# AUDIO_LINEOUT.net
KiCad netlist of a schematic drawn in Altium Designer
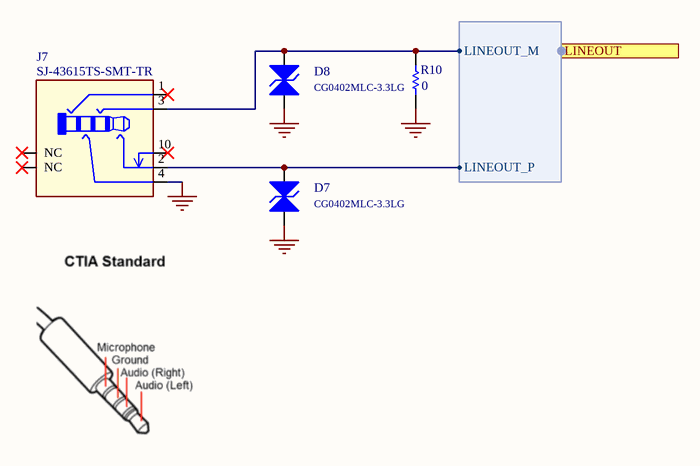
[diagram p0: AUDIO_LINEOUT.SchDoc]

(export (version "E")
  (design (tool "Eeschema 10.0.6"))
  (components
    (comp (ref "D7")
      (value "CG0402MLC-3.3LG")
      (footprint "0402")
      (description "DIODE TVS SMD 0402 3.3V ESD PROTECTION")
      (fields (field (name "MANUFACTURER") "Bourns"))
      (libsource (lib "Clean") (part "Diode Bidirectional"))
    )
    (comp (ref "D8")
      (value "CG0402MLC-3.3LG")
      (footprint "0402")
      (description "DIODE TVS SMD 0402 3.3V ESD PROTECTION")
      (fields (field (name "MANUFACTURER") "Bourns"))
      (libsource (lib "Clean") (part "Diode Bidirectional"))
    )
    (comp (ref "J7")
      (value "SJ-43615TS-SMT-TR")
      (footprint "SJ-43615TS-SMT-TR")
      (description "CONN Audio Jack 3.5mm, 4 conductor, tip switch, SMD mid mount")
      (fields (field (name "MANUFACTURER") "Same Sky"))
      (libsource (lib "Clean") (part "SJ-43615TS-SMT-TR-Symbol-1"))
    )
    (comp (ref "R10")
      (value "0")
      (footprint "RES-0402")
      (description "RES CHIP 0402 0R 1/16W")
      (fields (field (name "POWER") "62.5mW") (field (name "MANUFACTURER") "Vishay"))
      (libsource (lib "Clean") (part "RES"))
    )
  )
  (nets
    (net (code "3") (name "GND") (class "Default")
      (node (ref "D7") (pin "A") (pinfunction "A_A") (pintype "passive"))
      (node (ref "D8") (pin "A") (pinfunction "A_A") (pintype "passive"))
      (node (ref "J7") (pin "4") (pinfunction "4_4") (pintype "passive"))
      (node (ref "R10") (pin "1") (pinfunction "1_1") (pintype "passive"))
    )
    (net (code "4") (name "Net-(D7-PadC)") (class "Default")
      (node (ref "D7") (pin "C") (pinfunction "C_C") (pintype "passive"))
      (node (ref "J7") (pin "2") (pinfunction "2_2") (pintype "passive"))
    )
    (net (code "5") (name "Net-(D8-PadC)") (class "Default")
      (node (ref "D8") (pin "C") (pinfunction "C_C") (pintype "passive"))
      (node (ref "J7") (pin "3") (pinfunction "3_3") (pintype "passive"))
      (node (ref "R10") (pin "2") (pinfunction "2_2") (pintype "passive"))
    )
    (net (code "6") (name "unconnected-(J7-NC-Pad11)") (class "Default")
      (node (ref "J7") (pin "11") (pinfunction "NC_11") (pintype "passive+no_connect"))
    )
    (net (code "7") (name "unconnected-(J7-NC-Pad12)") (class "Default")
      (node (ref "J7") (pin "12") (pinfunction "NC_12") (pintype "passive+no_connect"))
    )
    (net (code "8") (name "unconnected-(J7-Pad1)") (class "Default")
      (node (ref "J7") (pin "1") (pinfunction "1_1") (pintype "passive+no_connect"))
    )
    (net (code "9") (name "unconnected-(J7-Pad10)") (class "Default")
      (node (ref "J7") (pin "10") (pinfunction "10_10") (pintype "passive+no_connect"))
    )
  )
)
